# PIC18F4550_Ref3-Mod.net
KiCad netlist of a schematic drawn in EAGLE
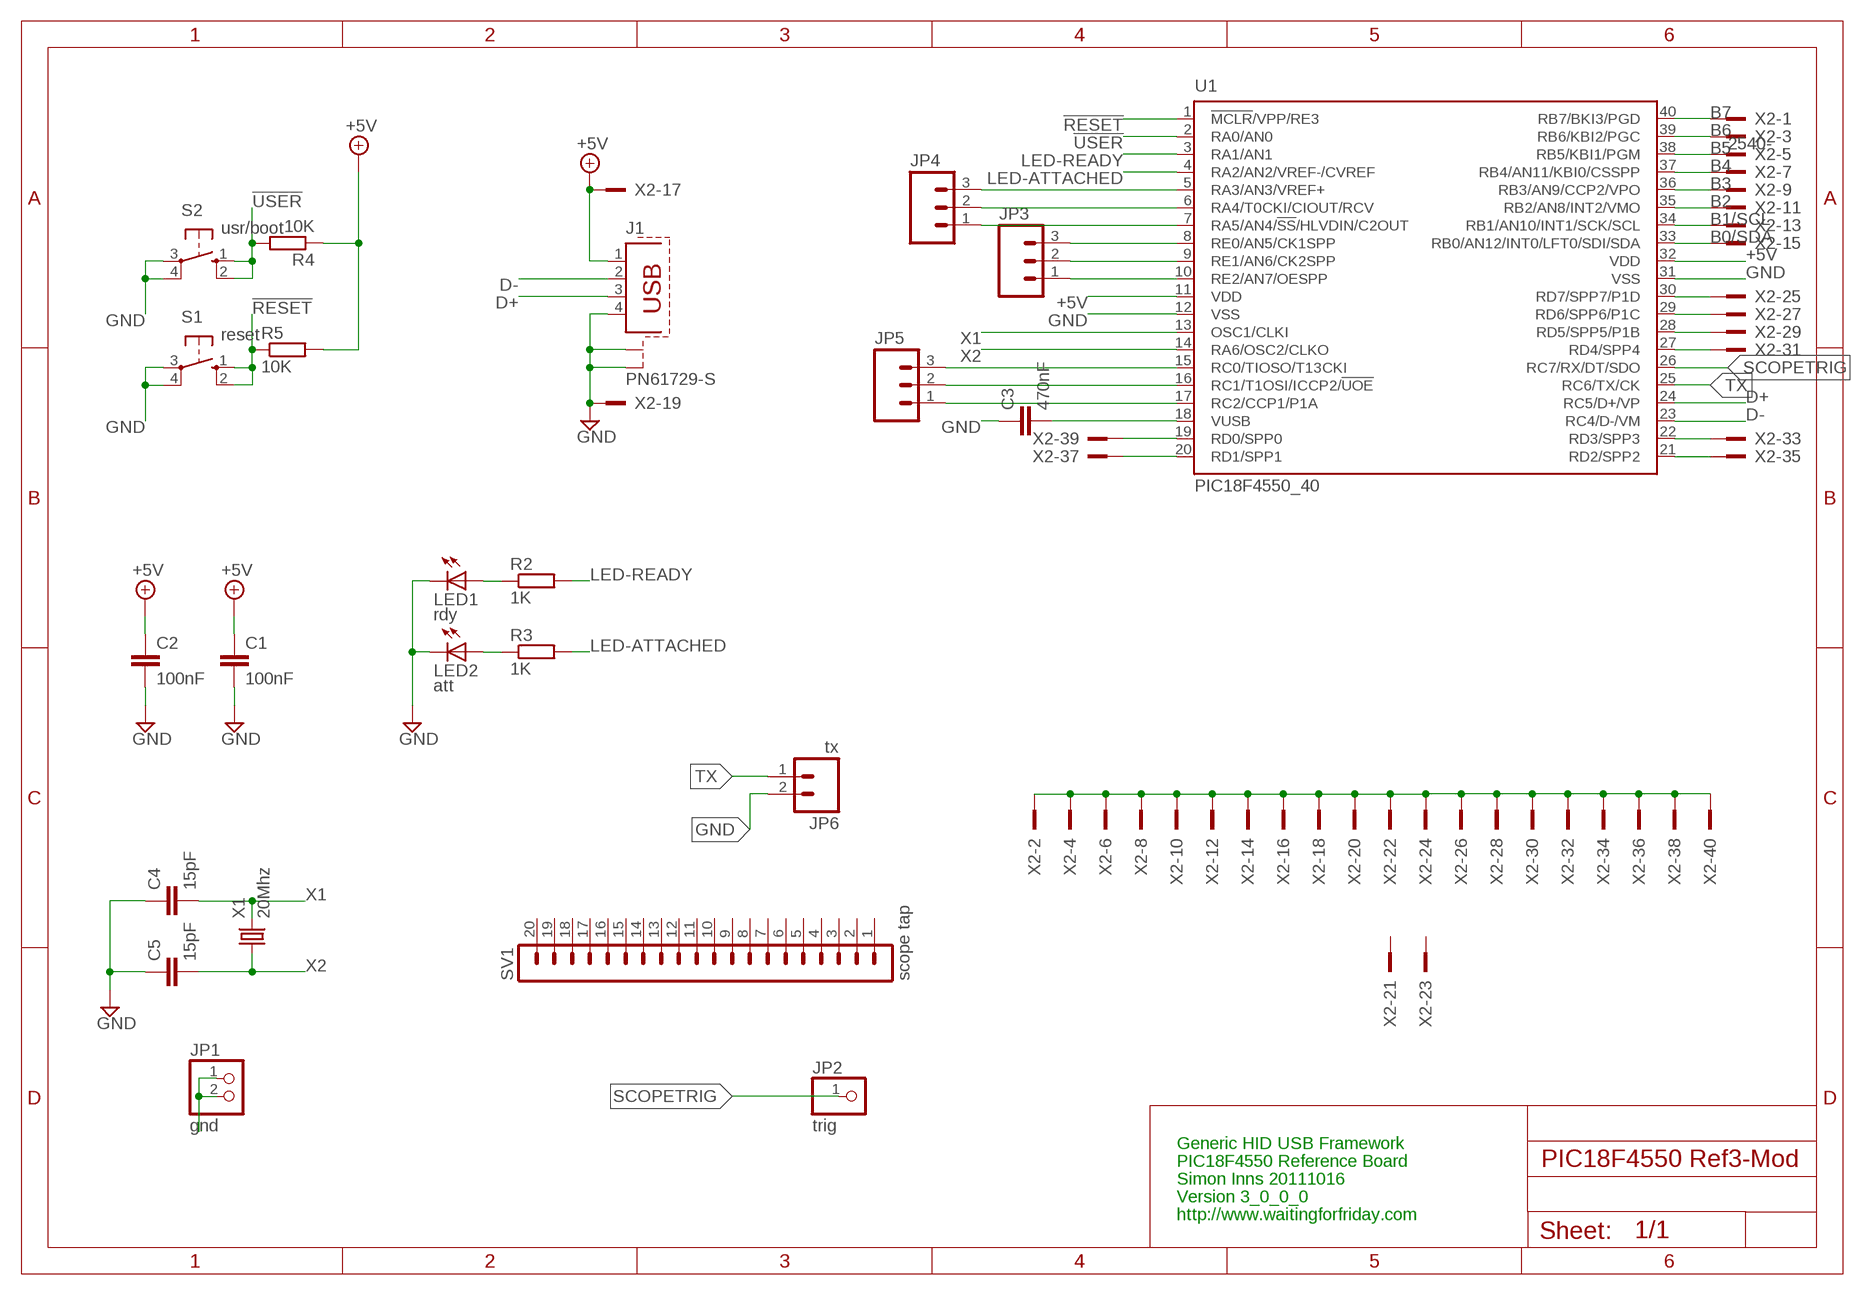
[diagram p0: schematic, sheet 1]

(export (version "E")
  (design (tool "Eeschema 10.0.6"))
  (components
    (comp (ref "C1")
      (value "100nF")
      (footprint "eagle-import:C025-025X050")
      (libsource (lib "eagle-import") (part "C-EU025-025X050"))
    )
    (comp (ref "C2")
      (value "100nF")
      (footprint "eagle-import:C025-025X050")
      (libsource (lib "eagle-import") (part "C-EU025-025X050"))
    )
    (comp (ref "C3")
      (value "470nF")
      (footprint "eagle-import:C025-025X050")
      (libsource (lib "eagle-import") (part "C-EU025-025X050"))
    )
    (comp (ref "C4")
      (value "15pF")
      (footprint "eagle-import:C050-024X044")
      (libsource (lib "eagle-import") (part "C-EU050-024X044"))
    )
    (comp (ref "C5")
      (value "15pF")
      (footprint "eagle-import:C050-024X044")
      (libsource (lib "eagle-import") (part "C-EU050-024X044"))
    )
    (comp (ref "J1")
      (value "PN61729-S")
      (footprint "eagle-import:PN61729-S")
      (libsource (lib "eagle-import") (part "PN61729-S"))
    )
    (comp (ref "JP1")
      (value "gnd")
      (footprint "eagle-import:1X02")
      (libsource (lib "eagle-import") (part "PINHD-1X2"))
    )
    (comp (ref "JP2")
      (value "trig")
      (footprint "eagle-import:1X01")
      (libsource (lib "eagle-import") (part "PINHD-1X1"))
    )
    (comp (ref "JP3")
      (value "M03PTH")
      (footprint "eagle-import:1X03")
      (libsource (lib "eagle-import") (part "M03PTH"))
    )
    (comp (ref "JP4")
      (value "M03PTH")
      (footprint "eagle-import:1X03")
      (libsource (lib "eagle-import") (part "M03PTH"))
    )
    (comp (ref "JP5")
      (value "M03PTH")
      (footprint "eagle-import:1X03")
      (libsource (lib "eagle-import") (part "M03PTH"))
    )
    (comp (ref "JP6")
      (value "tx")
      (footprint "eagle-import:1X02")
      (libsource (lib "eagle-import") (part "M02PTH"))
    )
    (comp (ref "LED1")
      (value "rdy")
      (footprint "eagle-import:LED3MM")
      (libsource (lib "eagle-import") (part "LED3MM"))
    )
    (comp (ref "LED2")
      (value "att")
      (footprint "eagle-import:LED3MM")
      (libsource (lib "eagle-import") (part "LED3MM"))
    )
    (comp (ref "R2")
      (value "1K")
      (footprint "eagle-import:0207_10")
      (libsource (lib "eagle-import") (part "R-EU_0207/10"))
    )
    (comp (ref "R3")
      (value "1K")
      (footprint "eagle-import:0207_10")
      (libsource (lib "eagle-import") (part "R-EU_0207/10"))
    )
    (comp (ref "R4")
      (value "10K")
      (footprint "eagle-import:0207_10")
      (libsource (lib "eagle-import") (part "R-EU_0207/10"))
    )
    (comp (ref "R5")
      (value "10K")
      (footprint "eagle-import:0207_10")
      (libsource (lib "eagle-import") (part "R-EU_0207/10"))
    )
    (comp (ref "S1")
      (value "reset")
      (footprint "eagle-import:B3F-10XX")
      (fields (field (name "MPN") "B3F-1000"))
      (libsource (lib "eagle-import") (part "10-XX"))
    )
    (comp (ref "S2")
      (value "usr/boot")
      (footprint "eagle-import:B3F-10XX")
      (fields (field (name "MPN") "B3F-1000"))
      (libsource (lib "eagle-import") (part "10-XX"))
    )
    (comp (ref "SV1")
      (value "scope tap")
      (footprint "eagle-import:MA20-1")
      (libsource (lib "eagle-import") (part "MA20-1"))
    )
    (comp (ref "U1")
      (value "PIC18F4550_40")
      (footprint "eagle-import:DIL40")
      (fields (field (name "MF") "MICROCHIP") (field (name "MPN") "PIC18F4550-I/P"))
      (libsource (lib "eagle-import") (part "PIC18F4_40550"))
    )
    (comp (ref "X1")
      (value "20Mhz")
      (footprint "eagle-import:HC49U-V")
      (libsource (lib "eagle-import") (part "CRYSTALHC49U-V"))
    )
    (comp (ref "X2")
      (value "2540-")
      (footprint "eagle-import:PAK100_2500-40")
      (libsource (lib "eagle-import") (part "2540-"))
    )
  )
  (nets
    (net (code "1") (name "+5V") (class "Default")
      (node (ref "C1") (pin "1") (pinfunction "1_1") (pintype "passive"))
      (node (ref "C2") (pin "1") (pinfunction "1_1") (pintype "passive"))
      (node (ref "J1") (pin "1") (pinfunction "1_1") (pintype "passive"))
      (node (ref "R4") (pin "1") (pinfunction "1_1") (pintype "passive"))
      (node (ref "R5") (pin "2") (pinfunction "2_2") (pintype "passive"))
      (node (ref "U1") (pin "11") (pinfunction "VDD_11") (pintype "power_in"))
      (node (ref "U1") (pin "32") (pinfunction "VDD_32") (pintype "power_in"))
      (node (ref "X2") (pin "17") (pinfunction "KL_17") (pintype "passive"))
    )
    (net (code "2") (name "/B0{slash}SDA") (class "Default")
      (node (ref "U1") (pin "33") (pinfunction "RB0/AN12/INT0/LFT0/SDI/SDA_33") (pintype "bidirectional"))
      (node (ref "X2") (pin "15") (pinfunction "KL_15") (pintype "passive"))
    )
    (net (code "3") (name "/B1{slash}SCL") (class "Default")
      (node (ref "U1") (pin "34") (pinfunction "RB1/AN10/INT1/SCK/SCL_34") (pintype "bidirectional"))
      (node (ref "X2") (pin "13") (pinfunction "KL_13") (pintype "passive"))
    )
    (net (code "4") (name "/B2") (class "Default")
      (node (ref "U1") (pin "35") (pinfunction "RB2/AN8/INT2/VMO_35") (pintype "bidirectional"))
      (node (ref "X2") (pin "11") (pinfunction "KL_11") (pintype "passive"))
    )
    (net (code "5") (name "/B3") (class "Default")
      (node (ref "U1") (pin "36") (pinfunction "RB3/AN9/CCP2/VPO_36") (pintype "bidirectional"))
      (node (ref "X2") (pin "9") (pinfunction "KL_9") (pintype "passive"))
    )
    (net (code "6") (name "/B4") (class "Default")
      (node (ref "U1") (pin "37") (pinfunction "RB4/AN11/KBI0/CSSPP_37") (pintype "bidirectional"))
      (node (ref "X2") (pin "7") (pinfunction "KL_7") (pintype "passive"))
    )
    (net (code "7") (name "/B5") (class "Default")
      (node (ref "U1") (pin "38") (pinfunction "RB5/KBI1/PGM_38") (pintype "bidirectional"))
      (node (ref "X2") (pin "5") (pinfunction "KL_5") (pintype "passive"))
    )
    (net (code "8") (name "/B6") (class "Default")
      (node (ref "U1") (pin "39") (pinfunction "RB6/KBI2/PGC_39") (pintype "bidirectional"))
      (node (ref "X2") (pin "3") (pinfunction "KL_3") (pintype "passive"))
    )
    (net (code "9") (name "/B7") (class "Default")
      (node (ref "U1") (pin "40") (pinfunction "RB7/BKI3/PGD_40") (pintype "bidirectional"))
      (node (ref "X2") (pin "1") (pinfunction "KL_1") (pintype "passive"))
    )
    (net (code "10") (name "/D+") (class "Default")
      (node (ref "J1") (pin "3") (pinfunction "3_3") (pintype "passive"))
      (node (ref "U1") (pin "24") (pinfunction "RC5/D+/VP_24") (pintype "bidirectional"))
    )
    (net (code "11") (name "/D-") (class "Default")
      (node (ref "J1") (pin "2") (pinfunction "2_2") (pintype "passive"))
      (node (ref "U1") (pin "23") (pinfunction "RC4/D-/VM_23") (pintype "bidirectional"))
    )
    (net (code "12") (name "/LED-ATTACHED") (class "Default")
      (node (ref "R3") (pin "2") (pinfunction "2_2") (pintype "passive"))
      (node (ref "U1") (pin "4") (pinfunction "RA2/AN2/VREF-/CVREF_4") (pintype "bidirectional"))
    )
    (net (code "13") (name "/LED-READY") (class "Default")
      (node (ref "R2") (pin "2") (pinfunction "2_2") (pintype "passive"))
      (node (ref "U1") (pin "3") (pinfunction "RA1/AN1_3") (pintype "bidirectional"))
    )
    (net (code "14") (name "/X1") (class "Default")
      (node (ref "C4") (pin "2") (pinfunction "2_2") (pintype "passive"))
      (node (ref "U1") (pin "13") (pinfunction "OSC1/CLKI_13") (pintype "input"))
      (node (ref "X1") (pin "2") (pinfunction "2_2") (pintype "passive"))
    )
    (net (code "15") (name "/X2") (class "Default")
      (node (ref "C5") (pin "2") (pinfunction "2_2") (pintype "passive"))
      (node (ref "U1") (pin "14") (pinfunction "RA6/OSC2/CLKO_14") (pintype "output"))
      (node (ref "X1") (pin "1") (pinfunction "1_1") (pintype "passive"))
    )
    (net (code "16") (name "/~{RESET}") (class "Default")
      (node (ref "R5") (pin "1") (pinfunction "1_1") (pintype "passive"))
      (node (ref "S1") (pin "1") (pinfunction "S_1") (pintype "passive"))
      (node (ref "S1") (pin "2") (pinfunction "S1_2") (pintype "passive"))
      (node (ref "U1") (pin "1") (pinfunction "~{MCLR}/VPP/RE3_1") (pintype "input"))
    )
    (net (code "17") (name "/~{USER}") (class "Default")
      (node (ref "R4") (pin "2") (pinfunction "2_2") (pintype "passive"))
      (node (ref "S2") (pin "1") (pinfunction "S_1") (pintype "passive"))
      (node (ref "S2") (pin "2") (pinfunction "S1_2") (pintype "passive"))
      (node (ref "U1") (pin "2") (pinfunction "RA0/AN0_2") (pintype "bidirectional"))
    )
    (net (code "18") (name "GND") (class "Default")
      (node (ref "C1") (pin "2") (pinfunction "2_2") (pintype "passive"))
      (node (ref "C2") (pin "2") (pinfunction "2_2") (pintype "passive"))
      (node (ref "C3") (pin "1") (pinfunction "1_1") (pintype "passive"))
      (node (ref "C4") (pin "1") (pinfunction "1_1") (pintype "passive"))
      (node (ref "C5") (pin "1") (pinfunction "1_1") (pintype "passive"))
      (node (ref "J1") (pin "4") (pinfunction "4_4") (pintype "passive"))
      (node (ref "J1") (pin "S1") (pinfunction "S1_S1") (pintype "passive"))
      (node (ref "J1") (pin "S2") (pinfunction "S2_S2") (pintype "passive"))
      (node (ref "JP1") (pin "1") (pinfunction "1_1") (pintype "passive"))
      (node (ref "JP1") (pin "2") (pinfunction "2_2") (pintype "passive"))
      (node (ref "JP6") (pin "2") (pinfunction "2_2") (pintype "passive"))
      (node (ref "LED1") (pin "K") (pinfunction "C_K") (pintype "passive"))
      (node (ref "LED2") (pin "K") (pinfunction "C_K") (pintype "passive"))
      (node (ref "S1") (pin "3") (pinfunction "P_3") (pintype "passive"))
      (node (ref "S1") (pin "4") (pinfunction "P1_4") (pintype "passive"))
      (node (ref "S2") (pin "3") (pinfunction "P_3") (pintype "passive"))
      (node (ref "S2") (pin "4") (pinfunction "P1_4") (pintype "passive"))
      (node (ref "U1") (pin "12") (pinfunction "VSS_12") (pintype "power_in"))
      (node (ref "U1") (pin "31") (pinfunction "VSS_31") (pintype "power_in"))
      (node (ref "X2") (pin "10") (pinfunction "KL_10") (pintype "passive"))
      (node (ref "X2") (pin "12") (pinfunction "KL_12") (pintype "passive"))
      (node (ref "X2") (pin "14") (pinfunction "KL_14") (pintype "passive"))
      (node (ref "X2") (pin "16") (pinfunction "KL_16") (pintype "passive"))
      (node (ref "X2") (pin "18") (pinfunction "KL_18") (pintype "passive"))
      (node (ref "X2") (pin "19") (pinfunction "KL_19") (pintype "passive"))
      (node (ref "X2") (pin "2") (pinfunction "KL_2") (pintype "passive"))
      (node (ref "X2") (pin "20") (pinfunction "KL_20") (pintype "passive"))
      (node (ref "X2") (pin "22") (pinfunction "KL_22") (pintype "passive"))
      (node (ref "X2") (pin "24") (pinfunction "KL_24") (pintype "passive"))
      (node (ref "X2") (pin "26") (pinfunction "KL_26") (pintype "passive"))
      (node (ref "X2") (pin "28") (pinfunction "KL_28") (pintype "passive"))
      (node (ref "X2") (pin "30") (pinfunction "KL_30") (pintype "passive"))
      (node (ref "X2") (pin "32") (pinfunction "KL_32") (pintype "passive"))
      (node (ref "X2") (pin "34") (pinfunction "KL_34") (pintype "passive"))
      (node (ref "X2") (pin "36") (pinfunction "KL_36") (pintype "passive"))
      (node (ref "X2") (pin "38") (pinfunction "KL_38") (pintype "passive"))
      (node (ref "X2") (pin "4") (pinfunction "KL_4") (pintype "passive"))
      (node (ref "X2") (pin "40") (pinfunction "KL_40") (pintype "passive"))
      (node (ref "X2") (pin "6") (pinfunction "KL_6") (pintype "passive"))
      (node (ref "X2") (pin "8") (pinfunction "KL_8") (pintype "passive"))
    )
    (net (code "19") (name "Net-(LED1-PadA)") (class "Default")
      (node (ref "LED1") (pin "A") (pinfunction "A_A") (pintype "passive"))
      (node (ref "R2") (pin "1") (pinfunction "1_1") (pintype "passive"))
    )
    (net (code "20") (name "Net-(LED2-PadA)") (class "Default")
      (node (ref "LED2") (pin "A") (pinfunction "A_A") (pintype "passive"))
      (node (ref "R3") (pin "1") (pinfunction "1_1") (pintype "passive"))
    )
    (net (code "21") (name "Net-(U1-RA3{slash}AN3{slash}VREF+)") (class "Default")
      (node (ref "JP4") (pin "3") (pinfunction "3_3") (pintype "passive"))
      (node (ref "U1") (pin "5") (pinfunction "RA3/AN3/VREF+_5") (pintype "bidirectional"))
    )
    (net (code "22") (name "Net-(U1-RA4{slash}T0CKI{slash}CIOUT{slash}RCV)") (class "Default")
      (node (ref "JP4") (pin "2") (pinfunction "2_2") (pintype "passive"))
      (node (ref "U1") (pin "6") (pinfunction "RA4/T0CKI/CIOUT/RCV_6") (pintype "bidirectional"))
    )
    (net (code "23") (name "Net-(U1-RA5{slash}AN4{slash}~{SS}{slash}HLVDIN{slash}C2OUT)") (class "Default")
      (node (ref "JP4") (pin "1") (pinfunction "1_1") (pintype "passive"))
      (node (ref "U1") (pin "7") (pinfunction "RA5/AN4/~{SS}/HLVDIN/C2OUT_7") (pintype "bidirectional"))
    )
    (net (code "24") (name "Net-(U1-RC0{slash}TIOSO{slash}T13CKI)") (class "Default")
      (node (ref "JP5") (pin "3") (pinfunction "3_3") (pintype "passive"))
      (node (ref "U1") (pin "15") (pinfunction "RC0/TIOSO/T13CKI_15") (pintype "bidirectional"))
    )
    (net (code "25") (name "Net-(U1-RC1{slash}T1OSI{slash}ICCP2{slash}~{UOE})") (class "Default")
      (node (ref "JP5") (pin "2") (pinfunction "2_2") (pintype "passive"))
      (node (ref "U1") (pin "16") (pinfunction "RC1/T1OSI/ICCP2/~{UOE}_16") (pintype "bidirectional"))
    )
    (net (code "26") (name "Net-(U1-RC2{slash}CCP1{slash}P1A)") (class "Default")
      (node (ref "JP5") (pin "1") (pinfunction "1_1") (pintype "passive"))
      (node (ref "U1") (pin "17") (pinfunction "RC2/CCP1/P1A_17") (pintype "bidirectional"))
    )
    (net (code "27") (name "Net-(U1-RD0{slash}SPP0)") (class "Default")
      (node (ref "U1") (pin "19") (pinfunction "RD0/SPP0_19") (pintype "bidirectional"))
      (node (ref "X2") (pin "39") (pinfunction "KL_39") (pintype "passive"))
    )
    (net (code "28") (name "Net-(U1-RD1{slash}SPP1)") (class "Default")
      (node (ref "U1") (pin "20") (pinfunction "RD1/SPP1_20") (pintype "bidirectional"))
      (node (ref "X2") (pin "37") (pinfunction "KL_37") (pintype "passive"))
    )
    (net (code "29") (name "Net-(U1-RD2{slash}SPP2)") (class "Default")
      (node (ref "U1") (pin "21") (pinfunction "RD2/SPP2_21") (pintype "bidirectional"))
      (node (ref "X2") (pin "35") (pinfunction "KL_35") (pintype "passive"))
    )
    (net (code "30") (name "Net-(U1-RD3{slash}SPP3)") (class "Default")
      (node (ref "U1") (pin "22") (pinfunction "RD3/SPP3_22") (pintype "bidirectional"))
      (node (ref "X2") (pin "33") (pinfunction "KL_33") (pintype "passive"))
    )
    (net (code "31") (name "Net-(U1-RD4{slash}SPP4)") (class "Default")
      (node (ref "U1") (pin "27") (pinfunction "RD4/SPP4_27") (pintype "bidirectional"))
      (node (ref "X2") (pin "31") (pinfunction "KL_31") (pintype "passive"))
    )
    (net (code "32") (name "Net-(U1-RD5{slash}SPP5{slash}P1B)") (class "Default")
      (node (ref "U1") (pin "28") (pinfunction "RD5/SPP5/P1B_28") (pintype "bidirectional"))
      (node (ref "X2") (pin "29") (pinfunction "KL_29") (pintype "passive"))
    )
    (net (code "33") (name "Net-(U1-RD6{slash}SPP6{slash}P1C)") (class "Default")
      (node (ref "U1") (pin "29") (pinfunction "RD6/SPP6/P1C_29") (pintype "bidirectional"))
      (node (ref "X2") (pin "27") (pinfunction "KL_27") (pintype "passive"))
    )
    (net (code "34") (name "Net-(U1-RD7{slash}SPP7{slash}P1D)") (class "Default")
      (node (ref "U1") (pin "30") (pinfunction "RD7/SPP7/P1D_30") (pintype "bidirectional"))
      (node (ref "X2") (pin "25") (pinfunction "KL_25") (pintype "passive"))
    )
    (net (code "35") (name "Net-(U1-RE0{slash}AN5{slash}CK1SPP)") (class "Default")
      (node (ref "JP3") (pin "3") (pinfunction "3_3") (pintype "passive"))
      (node (ref "U1") (pin "8") (pinfunction "RE0/AN5/CK1SPP_8") (pintype "bidirectional"))
    )
    (net (code "36") (name "Net-(U1-RE1{slash}AN6{slash}CK2SPP)") (class "Default")
      (node (ref "JP3") (pin "2") (pinfunction "2_2") (pintype "passive"))
      (node (ref "U1") (pin "9") (pinfunction "RE1/AN6/CK2SPP_9") (pintype "bidirectional"))
    )
    (net (code "37") (name "Net-(U1-RE2{slash}AN7{slash}OESPP)") (class "Default")
      (node (ref "JP3") (pin "1") (pinfunction "1_1") (pintype "passive"))
      (node (ref "U1") (pin "10") (pinfunction "RE2/AN7/OESPP_10") (pintype "bidirectional"))
    )
    (net (code "38") (name "Net-(U1-VUSB)") (class "Default")
      (node (ref "C3") (pin "2") (pinfunction "2_2") (pintype "passive"))
      (node (ref "U1") (pin "18") (pinfunction "VUSB_18") (pintype "bidirectional"))
    )
    (net (code "39") (name "SCOPETRIG") (class "Default")
      (node (ref "JP2") (pin "1") (pinfunction "1_1") (pintype "passive"))
      (node (ref "U1") (pin "26") (pinfunction "RC7/RX/DT/SDO_26") (pintype "bidirectional"))
    )
    (net (code "40") (name "TX") (class "Default")
      (node (ref "JP6") (pin "1") (pinfunction "1_1") (pintype "passive"))
      (node (ref "U1") (pin "25") (pinfunction "RC6/TX/CK_25") (pintype "bidirectional"))
    )
    (net (code "41") (name "unconnected-(SV1-Pad1)") (class "Default")
      (node (ref "SV1") (pin "1") (pinfunction "1_1") (pintype "passive"))
    )
    (net (code "42") (name "unconnected-(SV1-Pad2)") (class "Default")
      (node (ref "SV1") (pin "2") (pinfunction "2_2") (pintype "passive"))
    )
    (net (code "43") (name "unconnected-(SV1-Pad3)") (class "Default")
      (node (ref "SV1") (pin "3") (pinfunction "3_3") (pintype "passive"))
    )
    (net (code "44") (name "unconnected-(SV1-Pad4)") (class "Default")
      (node (ref "SV1") (pin "4") (pinfunction "4_4") (pintype "passive"))
    )
    (net (code "45") (name "unconnected-(SV1-Pad5)") (class "Default")
      (node (ref "SV1") (pin "5") (pinfunction "5_5") (pintype "passive"))
    )
    (net (code "46") (name "unconnected-(SV1-Pad6)") (class "Default")
      (node (ref "SV1") (pin "6") (pinfunction "6_6") (pintype "passive"))
    )
    (net (code "47") (name "unconnected-(SV1-Pad7)") (class "Default")
      (node (ref "SV1") (pin "7") (pinfunction "7_7") (pintype "passive"))
    )
    (net (code "48") (name "unconnected-(SV1-Pad8)") (class "Default")
      (node (ref "SV1") (pin "8") (pinfunction "8_8") (pintype "passive"))
    )
    (net (code "49") (name "unconnected-(SV1-Pad9)") (class "Default")
      (node (ref "SV1") (pin "9") (pinfunction "9_9") (pintype "passive"))
    )
    (net (code "50") (name "unconnected-(SV1-Pad10)") (class "Default")
      (node (ref "SV1") (pin "10") (pinfunction "10_10") (pintype "passive"))
    )
    (net (code "51") (name "unconnected-(SV1-Pad11)") (class "Default")
      (node (ref "SV1") (pin "11") (pinfunction "11_11") (pintype "passive"))
    )
    (net (code "52") (name "unconnected-(SV1-Pad12)") (class "Default")
      (node (ref "SV1") (pin "12") (pinfunction "12_12") (pintype "passive"))
    )
    (net (code "53") (name "unconnected-(SV1-Pad13)") (class "Default")
      (node (ref "SV1") (pin "13") (pinfunction "13_13") (pintype "passive"))
    )
    (net (code "54") (name "unconnected-(SV1-Pad14)") (class "Default")
      (node (ref "SV1") (pin "14") (pinfunction "14_14") (pintype "passive"))
    )
    (net (code "55") (name "unconnected-(SV1-Pad15)") (class "Default")
      (node (ref "SV1") (pin "15") (pinfunction "15_15") (pintype "passive"))
    )
    (net (code "56") (name "unconnected-(SV1-Pad16)") (class "Default")
      (node (ref "SV1") (pin "16") (pinfunction "16_16") (pintype "passive"))
    )
    (net (code "57") (name "unconnected-(SV1-Pad17)") (class "Default")
      (node (ref "SV1") (pin "17") (pinfunction "17_17") (pintype "passive"))
    )
    (net (code "58") (name "unconnected-(SV1-Pad18)") (class "Default")
      (node (ref "SV1") (pin "18") (pinfunction "18_18") (pintype "passive"))
    )
    (net (code "59") (name "unconnected-(SV1-Pad19)") (class "Default")
      (node (ref "SV1") (pin "19") (pinfunction "19_19") (pintype "passive"))
    )
    (net (code "60") (name "unconnected-(SV1-Pad20)") (class "Default")
      (node (ref "SV1") (pin "20") (pinfunction "20_20") (pintype "passive"))
    )
    (net (code "61") (name "unconnected-(X2N-KL-Pad21)") (class "Default")
      (node (ref "X2") (pin "21") (pinfunction "KL_21") (pintype "passive"))
    )
    (net (code "62") (name "unconnected-(X2P-KL-Pad23)") (class "Default")
      (node (ref "X2") (pin "23") (pinfunction "KL_23") (pintype "passive"))
    )
  )
)
